# signal_generator_schematic_-_botttom.net
KiCad netlist of a schematic drawn in EAGLE
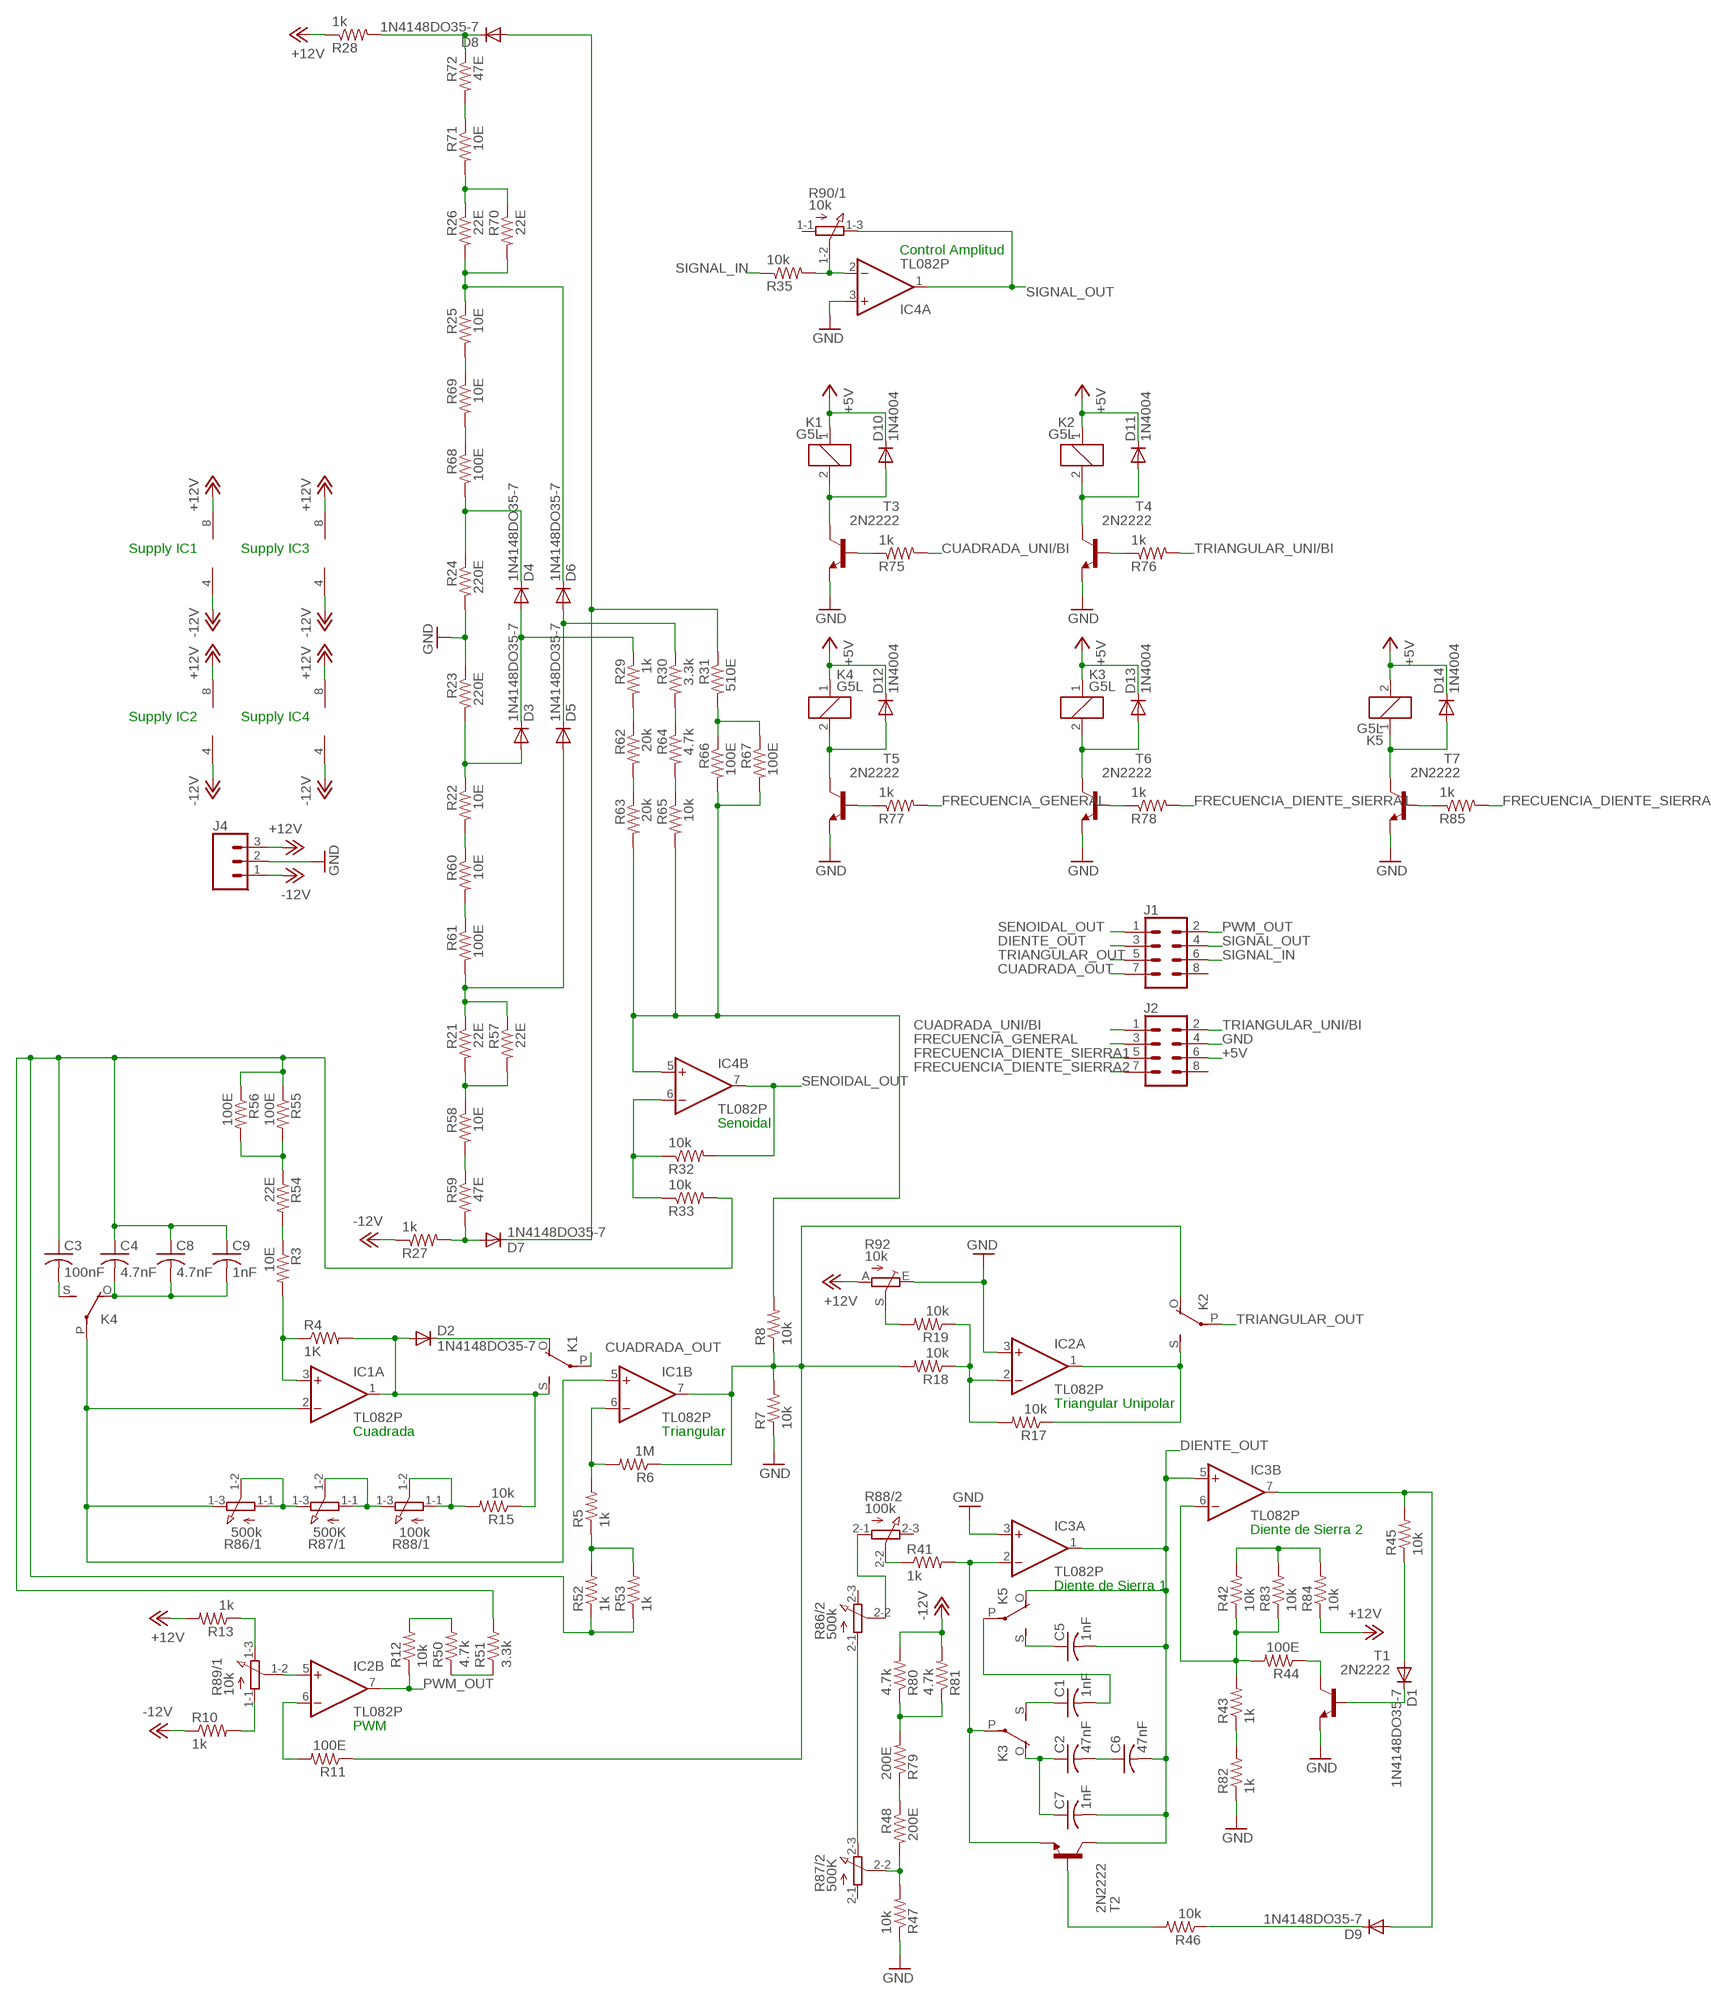
[diagram p0: schematic, sheet 1]

(export (version "E")
  (design (tool "Eeschema 10.0.6"))
  (components
    (comp (ref "C1")
      (value "1nF")
      (footprint "eagle-import:C150-054X183")
      (libsource (lib "eagle-import") (part "C-US150-054X183"))
    )
    (comp (ref "C2")
      (value "47nF")
      (footprint "eagle-import:C150-054X183")
      (libsource (lib "eagle-import") (part "C-US150-054X183"))
    )
    (comp (ref "C3")
      (value "100nF")
      (footprint "eagle-import:C150-084X183")
      (libsource (lib "eagle-import") (part "C-US150-084X183"))
    )
    (comp (ref "C4")
      (value "4.7nF")
      (footprint "eagle-import:C102-043X133")
      (libsource (lib "eagle-import") (part "C-US102-043X133"))
    )
    (comp (ref "C5")
      (value "1nF")
      (footprint "eagle-import:C150-054X183")
      (libsource (lib "eagle-import") (part "C-US150-054X183"))
    )
    (comp (ref "C6")
      (value "47nF")
      (footprint "eagle-import:C150-054X183")
      (libsource (lib "eagle-import") (part "C-US150-054X183"))
    )
    (comp (ref "C7")
      (value "1nF")
      (footprint "eagle-import:C150-054X183")
      (libsource (lib "eagle-import") (part "C-US150-054X183"))
    )
    (comp (ref "C8")
      (value "4.7nF")
      (footprint "eagle-import:C102-043X133")
      (libsource (lib "eagle-import") (part "C-US102-043X133"))
    )
    (comp (ref "C9")
      (value "1nF")
      (footprint "eagle-import:C150-054X183")
      (libsource (lib "eagle-import") (part "C-US150-054X183"))
    )
    (comp (ref "D1")
      (value "1N4148DO35-7")
      (footprint "eagle-import:DO35-7")
      (libsource (lib "eagle-import") (part "1N4148DO35-7"))
    )
    (comp (ref "D2")
      (value "1N4148DO35-7")
      (footprint "eagle-import:DO35-7")
      (libsource (lib "eagle-import") (part "1N4148DO35-7"))
    )
    (comp (ref "D3")
      (value "1N4148DO35-7")
      (footprint "eagle-import:DO35-7")
      (libsource (lib "eagle-import") (part "1N4148DO35-7"))
    )
    (comp (ref "D4")
      (value "1N4148DO35-7")
      (footprint "eagle-import:DO35-7")
      (libsource (lib "eagle-import") (part "1N4148DO35-7"))
    )
    (comp (ref "D5")
      (value "1N4148DO35-7")
      (footprint "eagle-import:DO35-7")
      (libsource (lib "eagle-import") (part "1N4148DO35-7"))
    )
    (comp (ref "D6")
      (value "1N4148DO35-7")
      (footprint "eagle-import:DO35-7")
      (libsource (lib "eagle-import") (part "1N4148DO35-7"))
    )
    (comp (ref "D7")
      (value "1N4148DO35-7")
      (footprint "eagle-import:DO35-7")
      (libsource (lib "eagle-import") (part "1N4148DO35-7"))
    )
    (comp (ref "D8")
      (value "1N4148DO35-7")
      (footprint "eagle-import:DO35-7")
      (libsource (lib "eagle-import") (part "1N4148DO35-7"))
    )
    (comp (ref "D9")
      (value "1N4148DO35-7")
      (footprint "eagle-import:DO35-7")
      (libsource (lib "eagle-import") (part "1N4148DO35-7"))
    )
    (comp (ref "D10")
      (value "1N4004")
      (footprint "eagle-import:DO41-10")
      (libsource (lib "eagle-import") (part "1N4004"))
    )
    (comp (ref "D11")
      (value "1N4004")
      (footprint "eagle-import:DO41-10")
      (libsource (lib "eagle-import") (part "1N4004"))
    )
    (comp (ref "D12")
      (value "1N4004")
      (footprint "eagle-import:DO41-10")
      (libsource (lib "eagle-import") (part "1N4004"))
    )
    (comp (ref "D13")
      (value "1N4004")
      (footprint "eagle-import:DO41-10")
      (libsource (lib "eagle-import") (part "1N4004"))
    )
    (comp (ref "D14")
      (value "1N4004")
      (footprint "eagle-import:DO41-10")
      (libsource (lib "eagle-import") (part "1N4004"))
    )
    (comp (ref "IC1")
      (value "TL082P")
      (footprint "eagle-import:DIL08")
      (libsource (lib "eagle-import") (part "TL082P"))
    )
    (comp (ref "IC2")
      (value "TL082P")
      (footprint "eagle-import:DIL08")
      (libsource (lib "eagle-import") (part "TL082P"))
    )
    (comp (ref "IC3")
      (value "TL082P")
      (footprint "eagle-import:DIL08")
      (libsource (lib "eagle-import") (part "TL082P"))
    )
    (comp (ref "IC4")
      (value "TL082P")
      (footprint "eagle-import:DIL08")
      (libsource (lib "eagle-import") (part "TL082P"))
    )
    (comp (ref "J1")
      (value "CONN_04X2")
      (footprint "eagle-import:2X4")
      (libsource (lib "eagle-import") (part "CONN_04X2"))
    )
    (comp (ref "J2")
      (value "CONN_04X2")
      (footprint "eagle-import:2X4")
      (libsource (lib "eagle-import") (part "CONN_04X2"))
    )
    (comp (ref "J4")
      (value "CONN_03-SCREW-5MM")
      (footprint "eagle-import:SCREWTERMINAL-5MM-3")
      (libsource (lib "eagle-import") (part "CONN_03-SCREW-5MM"))
    )
    (comp (ref "K1")
      (value "G5L")
      (footprint "eagle-import:G5LE")
      (libsource (lib "eagle-import") (part "G5L"))
    )
    (comp (ref "K2")
      (value "G5L")
      (footprint "eagle-import:G5LE")
      (libsource (lib "eagle-import") (part "G5L"))
    )
    (comp (ref "K3")
      (value "G5L")
      (footprint "eagle-import:G5LE")
      (libsource (lib "eagle-import") (part "G5L"))
    )
    (comp (ref "K4")
      (value "G5L")
      (footprint "eagle-import:G5LE")
      (libsource (lib "eagle-import") (part "G5L"))
    )
    (comp (ref "K5")
      (value "G5L")
      (footprint "eagle-import:G5LE")
      (libsource (lib "eagle-import") (part "G5L"))
    )
    (comp (ref "R3")
      (value "10E")
      (footprint "eagle-import:0207_7")
      (libsource (lib "eagle-import") (part "R-US_0207/7"))
    )
    (comp (ref "R4")
      (value "1K")
      (footprint "eagle-import:0207_7")
      (libsource (lib "eagle-import") (part "R-US_0207/7"))
    )
    (comp (ref "R5")
      (value "1k")
      (footprint "eagle-import:0207_7")
      (libsource (lib "eagle-import") (part "R-US_0207/7"))
    )
    (comp (ref "R6")
      (value "1M")
      (footprint "eagle-import:0207_7")
      (libsource (lib "eagle-import") (part "R-US_0207/7"))
    )
    (comp (ref "R7")
      (value "10k")
      (footprint "eagle-import:0207_7")
      (libsource (lib "eagle-import") (part "R-US_0207/7"))
    )
    (comp (ref "R8")
      (value "10k")
      (footprint "eagle-import:0207_7")
      (libsource (lib "eagle-import") (part "R-US_0207/7"))
    )
    (comp (ref "R10")
      (value "1k")
      (footprint "eagle-import:0207_7")
      (libsource (lib "eagle-import") (part "R-US_0207/7"))
    )
    (comp (ref "R11")
      (value "100E")
      (footprint "eagle-import:0207_7")
      (libsource (lib "eagle-import") (part "R-US_0207/7"))
    )
    (comp (ref "R12")
      (value "10k")
      (footprint "eagle-import:0207_7")
      (libsource (lib "eagle-import") (part "R-US_0207/7"))
    )
    (comp (ref "R13")
      (value "1k")
      (footprint "eagle-import:0207_7")
      (libsource (lib "eagle-import") (part "R-US_0207/7"))
    )
    (comp (ref "R15")
      (value "10k")
      (footprint "eagle-import:0207_7")
      (libsource (lib "eagle-import") (part "R-US_0207/7"))
    )
    (comp (ref "R17")
      (value "10k")
      (footprint "eagle-import:0207_7")
      (libsource (lib "eagle-import") (part "R-US_0207/7"))
    )
    (comp (ref "R18")
      (value "10k")
      (footprint "eagle-import:0207_7")
      (libsource (lib "eagle-import") (part "R-US_0207/7"))
    )
    (comp (ref "R19")
      (value "10k")
      (footprint "eagle-import:0207_7")
      (libsource (lib "eagle-import") (part "R-US_0207/7"))
    )
    (comp (ref "R21")
      (value "22E")
      (footprint "eagle-import:0207_7")
      (libsource (lib "eagle-import") (part "R-US_0207/7"))
    )
    (comp (ref "R22")
      (value "10E")
      (footprint "eagle-import:0207_7")
      (libsource (lib "eagle-import") (part "R-US_0207/7"))
    )
    (comp (ref "R23")
      (value "220E")
      (footprint "eagle-import:0207_7")
      (libsource (lib "eagle-import") (part "R-US_0207/7"))
    )
    (comp (ref "R24")
      (value "220E")
      (footprint "eagle-import:0207_7")
      (libsource (lib "eagle-import") (part "R-US_0207/7"))
    )
    (comp (ref "R25")
      (value "10E")
      (footprint "eagle-import:0207_7")
      (libsource (lib "eagle-import") (part "R-US_0207/7"))
    )
    (comp (ref "R26")
      (value "22E")
      (footprint "eagle-import:0207_7")
      (libsource (lib "eagle-import") (part "R-US_0207/7"))
    )
    (comp (ref "R27")
      (value "1k")
      (footprint "eagle-import:0207_7")
      (libsource (lib "eagle-import") (part "R-US_0207/7"))
    )
    (comp (ref "R28")
      (value "1k")
      (footprint "eagle-import:0207_7")
      (libsource (lib "eagle-import") (part "R-US_0207/7"))
    )
    (comp (ref "R29")
      (value "1k")
      (footprint "eagle-import:0207_7")
      (libsource (lib "eagle-import") (part "R-US_0207/7"))
    )
    (comp (ref "R30")
      (value "3.3k")
      (footprint "eagle-import:0207_7")
      (libsource (lib "eagle-import") (part "R-US_0207/7"))
    )
    (comp (ref "R31")
      (value "510E")
      (footprint "eagle-import:0207_7")
      (libsource (lib "eagle-import") (part "R-US_0207/7"))
    )
    (comp (ref "R32")
      (value "10k")
      (footprint "eagle-import:0207_7")
      (libsource (lib "eagle-import") (part "R-US_0207/7"))
    )
    (comp (ref "R33")
      (value "10k")
      (footprint "eagle-import:0207_7")
      (libsource (lib "eagle-import") (part "R-US_0207/7"))
    )
    (comp (ref "R35")
      (value "10k")
      (footprint "eagle-import:0207_7")
      (libsource (lib "eagle-import") (part "R-US_0207/7"))
    )
    (comp (ref "R41")
      (value "1k")
      (footprint "eagle-import:0207_7")
      (libsource (lib "eagle-import") (part "R-US_0207/7"))
    )
    (comp (ref "R42")
      (value "10k")
      (footprint "eagle-import:0207_7")
      (libsource (lib "eagle-import") (part "R-US_0207/7"))
    )
    (comp (ref "R43")
      (value "1k")
      (footprint "eagle-import:0207_7")
      (libsource (lib "eagle-import") (part "R-US_0207/7"))
    )
    (comp (ref "R44")
      (value "100E")
      (footprint "eagle-import:0207_7")
      (libsource (lib "eagle-import") (part "R-US_0207/7"))
    )
    (comp (ref "R45")
      (value "10k")
      (footprint "eagle-import:0207_7")
      (libsource (lib "eagle-import") (part "R-US_0207/7"))
    )
    (comp (ref "R46")
      (value "10k")
      (footprint "eagle-import:0207_7")
      (libsource (lib "eagle-import") (part "R-US_0207/7"))
    )
    (comp (ref "R47")
      (value "10k")
      (footprint "eagle-import:0207_7")
      (libsource (lib "eagle-import") (part "R-US_0207/7"))
    )
    (comp (ref "R48")
      (value "200E")
      (footprint "eagle-import:0207_7")
      (libsource (lib "eagle-import") (part "R-US_0207/7"))
    )
    (comp (ref "R50")
      (value "4.7k")
      (footprint "eagle-import:0207_7")
      (libsource (lib "eagle-import") (part "R-US_0207/7"))
    )
    (comp (ref "R51")
      (value "3.3k")
      (footprint "eagle-import:0207_7")
      (libsource (lib "eagle-import") (part "R-US_0207/7"))
    )
    (comp (ref "R52")
      (value "1k")
      (footprint "eagle-import:0207_7")
      (libsource (lib "eagle-import") (part "R-US_0207/7"))
    )
    (comp (ref "R53")
      (value "1k")
      (footprint "eagle-import:0207_7")
      (libsource (lib "eagle-import") (part "R-US_0207/7"))
    )
    (comp (ref "R54")
      (value "22E")
      (footprint "eagle-import:0207_7")
      (libsource (lib "eagle-import") (part "R-US_0207/7"))
    )
    (comp (ref "R55")
      (value "100E")
      (footprint "eagle-import:0207_7")
      (libsource (lib "eagle-import") (part "R-US_0207/7"))
    )
    (comp (ref "R56")
      (value "100E")
      (footprint "eagle-import:0207_7")
      (libsource (lib "eagle-import") (part "R-US_0207/7"))
    )
    (comp (ref "R57")
      (value "22E")
      (footprint "eagle-import:0207_7")
      (libsource (lib "eagle-import") (part "R-US_0207/7"))
    )
    (comp (ref "R58")
      (value "10E")
      (footprint "eagle-import:0207_7")
      (libsource (lib "eagle-import") (part "R-US_0207/7"))
    )
    (comp (ref "R59")
      (value "47E")
      (footprint "eagle-import:0207_7")
      (libsource (lib "eagle-import") (part "R-US_0207/7"))
    )
    (comp (ref "R60")
      (value "10E")
      (footprint "eagle-import:0207_7")
      (libsource (lib "eagle-import") (part "R-US_0207/7"))
    )
    (comp (ref "R61")
      (value "100E")
      (footprint "eagle-import:0207_7")
      (libsource (lib "eagle-import") (part "R-US_0207/7"))
    )
    (comp (ref "R62")
      (value "20k")
      (footprint "eagle-import:0207_7")
      (libsource (lib "eagle-import") (part "R-US_0207/7"))
    )
    (comp (ref "R63")
      (value "20k")
      (footprint "eagle-import:0207_7")
      (libsource (lib "eagle-import") (part "R-US_0207/7"))
    )
    (comp (ref "R64")
      (value "4.7k")
      (footprint "eagle-import:0207_7")
      (libsource (lib "eagle-import") (part "R-US_0207/7"))
    )
    (comp (ref "R65")
      (value "10k")
      (footprint "eagle-import:0207_7")
      (libsource (lib "eagle-import") (part "R-US_0207/7"))
    )
    (comp (ref "R66")
      (value "100E")
      (footprint "eagle-import:0207_7")
      (libsource (lib "eagle-import") (part "R-US_0207/7"))
    )
    (comp (ref "R67")
      (value "100E")
      (footprint "eagle-import:0207_7")
      (libsource (lib "eagle-import") (part "R-US_0207/7"))
    )
    (comp (ref "R68")
      (value "100E")
      (footprint "eagle-import:0207_7")
      (libsource (lib "eagle-import") (part "R-US_0207/7"))
    )
    (comp (ref "R69")
      (value "10E")
      (footprint "eagle-import:0207_7")
      (libsource (lib "eagle-import") (part "R-US_0207/7"))
    )
    (comp (ref "R70")
      (value "22E")
      (footprint "eagle-import:0207_7")
      (libsource (lib "eagle-import") (part "R-US_0207/7"))
    )
    (comp (ref "R71")
      (value "10E")
      (footprint "eagle-import:0207_7")
      (libsource (lib "eagle-import") (part "R-US_0207/7"))
    )
    (comp (ref "R72")
      (value "47E")
      (footprint "eagle-import:0207_7")
      (libsource (lib "eagle-import") (part "R-US_0207/7"))
    )
    (comp (ref "R75")
      (value "1k")
      (footprint "eagle-import:0207_7")
      (libsource (lib "eagle-import") (part "R-US_0207/7"))
    )
    (comp (ref "R76")
      (value "1k")
      (footprint "eagle-import:0207_7")
      (libsource (lib "eagle-import") (part "R-US_0207/7"))
    )
    (comp (ref "R77")
      (value "1k")
      (footprint "eagle-import:0207_7")
      (libsource (lib "eagle-import") (part "R-US_0207/7"))
    )
    (comp (ref "R78")
      (value "1k")
      (footprint "eagle-import:0207_7")
      (libsource (lib "eagle-import") (part "R-US_0207/7"))
    )
    (comp (ref "R79")
      (value "200E")
      (footprint "eagle-import:0207_7")
      (libsource (lib "eagle-import") (part "R-US_0207/7"))
    )
    (comp (ref "R80")
      (value "4.7k")
      (footprint "eagle-import:0207_7")
      (libsource (lib "eagle-import") (part "R-US_0207/7"))
    )
    (comp (ref "R81")
      (value "4.7k")
      (footprint "eagle-import:0207_7")
      (libsource (lib "eagle-import") (part "R-US_0207/7"))
    )
    (comp (ref "R82")
      (value "1k")
      (footprint "eagle-import:0207_7")
      (libsource (lib "eagle-import") (part "R-US_0207/7"))
    )
    (comp (ref "R83")
      (value "10k")
      (footprint "eagle-import:0207_7")
      (libsource (lib "eagle-import") (part "R-US_0207/7"))
    )
    (comp (ref "R84")
      (value "10k")
      (footprint "eagle-import:0207_7")
      (libsource (lib "eagle-import") (part "R-US_0207/7"))
    )
    (comp (ref "R85")
      (value "1k")
      (footprint "eagle-import:0207_7")
      (libsource (lib "eagle-import") (part "R-US_0207/7"))
    )
    (comp (ref "R86")
      (value "500k")
      (footprint "eagle-import:3RP_1610G")
      (libsource (lib "eagle-import") (part "3RP/1610G"))
    )
    (comp (ref "R87")
      (value "500K")
      (footprint "eagle-import:3RP_1610G")
      (libsource (lib "eagle-import") (part "3RP/1610G"))
    )
    (comp (ref "R88")
      (value "100k")
      (footprint "eagle-import:3RP_1610G")
      (libsource (lib "eagle-import") (part "3RP/1610G"))
    )
    (comp (ref "R89")
      (value "10k")
      (footprint "eagle-import:3RP_1610G")
      (libsource (lib "eagle-import") (part "3RP/1610G"))
    )
    (comp (ref "R90")
      (value "10k")
      (footprint "eagle-import:3RP_1610G")
      (libsource (lib "eagle-import") (part "3RP/1610G"))
    )
    (comp (ref "R92")
      (value "10k")
      (footprint "eagle-import:S63P")
      (libsource (lib "eagle-import") (part "TRIM_EU-S63P"))
    )
    (comp (ref "T1")
      (value "2N2222")
      (footprint "eagle-import:TO92-EBC-OVAL")
      (libsource (lib "eagle-import") (part "2N2222"))
    )
    (comp (ref "T2")
      (value "2N2222")
      (footprint "eagle-import:TO92-EBC-OVAL")
      (libsource (lib "eagle-import") (part "2N2222"))
    )
    (comp (ref "T3")
      (value "2N2222")
      (footprint "eagle-import:TO92-EBC-OVAL")
      (libsource (lib "eagle-import") (part "2N2222"))
    )
    (comp (ref "T4")
      (value "2N2222")
      (footprint "eagle-import:TO92-EBC-OVAL")
      (libsource (lib "eagle-import") (part "2N2222"))
    )
    (comp (ref "T5")
      (value "2N2222")
      (footprint "eagle-import:TO92-EBC-OVAL")
      (libsource (lib "eagle-import") (part "2N2222"))
    )
    (comp (ref "T6")
      (value "2N2222")
      (footprint "eagle-import:TO92-EBC-OVAL")
      (libsource (lib "eagle-import") (part "2N2222"))
    )
    (comp (ref "T7")
      (value "2N2222")
      (footprint "eagle-import:TO92-EBC-OVAL")
      (libsource (lib "eagle-import") (part "2N2222"))
    )
  )
  (nets
    (net (code "1") (name "+5V") (class "Default")
      (node (ref "D10") (pin "C") (pinfunction "C_C") (pintype "passive"))
      (node (ref "D11") (pin "C") (pinfunction "C_C") (pintype "passive"))
      (node (ref "D12") (pin "C") (pinfunction "C_C") (pintype "passive"))
      (node (ref "D13") (pin "C") (pinfunction "C_C") (pintype "passive"))
      (node (ref "D14") (pin "C") (pinfunction "C_C") (pintype "passive"))
      (node (ref "J2") (pin "6") (pinfunction "6_6") (pintype "passive"))
      (node (ref "K1") (pin "1") (pinfunction "1_1") (pintype "passive"))
      (node (ref "K2") (pin "1") (pinfunction "1_1") (pintype "passive"))
      (node (ref "K3") (pin "1") (pinfunction "1_1") (pintype "passive"))
      (node (ref "K4") (pin "1") (pinfunction "1_1") (pintype "passive"))
      (node (ref "K5") (pin "2") (pinfunction "2_2") (pintype "passive"))
    )
    (net (code "2") (name "+12V") (class "Default")
      (node (ref "IC1") (pin "8") (pinfunction "V+_8") (pintype "power_in"))
      (node (ref "IC2") (pin "8") (pinfunction "V+_8") (pintype "power_in"))
      (node (ref "IC3") (pin "8") (pinfunction "V+_8") (pintype "power_in"))
      (node (ref "IC4") (pin "8") (pinfunction "V+_8") (pintype "power_in"))
      (node (ref "J4") (pin "3") (pinfunction "3_3") (pintype "passive"))
      (node (ref "R13") (pin "2") (pinfunction "2_2") (pintype "passive"))
      (node (ref "R28") (pin "1") (pinfunction "1_1") (pintype "passive"))
      (node (ref "R84") (pin "1") (pinfunction "1_1") (pintype "passive"))
      (node (ref "R92") (pin "A") (pinfunction "A_A") (pintype "passive"))
    )
    (net (code "3") (name "-12V") (class "Default")
      (node (ref "IC1") (pin "4") (pinfunction "V-_4") (pintype "power_in"))
      (node (ref "IC2") (pin "4") (pinfunction "V-_4") (pintype "power_in"))
      (node (ref "IC3") (pin "4") (pinfunction "V-_4") (pintype "power_in"))
      (node (ref "IC4") (pin "4") (pinfunction "V-_4") (pintype "power_in"))
      (node (ref "J4") (pin "1") (pinfunction "1_1") (pintype "passive"))
      (node (ref "R10") (pin "1") (pinfunction "1_1") (pintype "passive"))
      (node (ref "R27") (pin "1") (pinfunction "1_1") (pintype "passive"))
      (node (ref "R80") (pin "2") (pinfunction "2_2") (pintype "passive"))
      (node (ref "R81") (pin "2") (pinfunction "2_2") (pintype "passive"))
    )
    (net (code "4") (name "/CUADRADA_OUT") (class "Default")
      (node (ref "J1") (pin "7") (pinfunction "7_7") (pintype "passive"))
      (node (ref "K1") (pin "P") (pinfunction "P_P") (pintype "passive"))
    )
    (net (code "5") (name "/CUADRADA_UNI{slash}BI") (class "Default")
      (node (ref "J2") (pin "1") (pinfunction "1_1") (pintype "passive"))
      (node (ref "R75") (pin "2") (pinfunction "2_2") (pintype "passive"))
    )
    (net (code "6") (name "/DIENTE_OUT") (class "Default")
      (node (ref "C5") (pin "2") (pinfunction "2_2") (pintype "passive"))
      (node (ref "C6") (pin "2") (pinfunction "2_2") (pintype "passive"))
      (node (ref "C7") (pin "2") (pinfunction "2_2") (pintype "passive"))
      (node (ref "IC3") (pin "1") (pinfunction "OUT_1") (pintype "output"))
      (node (ref "IC3") (pin "5") (pinfunction "+IN_5") (pintype "input"))
      (node (ref "J1") (pin "3") (pinfunction "3_3") (pintype "passive"))
      (node (ref "K5") (pin "O") (pinfunction "O_O") (pintype "passive"))
      (node (ref "T2") (pin "C") (pinfunction "C_C") (pintype "passive"))
    )
    (net (code "7") (name "/FRECUENCIA_DIENTE_SIERRA1") (class "Default")
      (node (ref "J2") (pin "5") (pinfunction "5_5") (pintype "passive"))
      (node (ref "R78") (pin "2") (pinfunction "2_2") (pintype "passive"))
    )
    (net (code "8") (name "/FRECUENCIA_DIENTE_SIERRA2") (class "Default")
      (node (ref "J2") (pin "7") (pinfunction "7_7") (pintype "passive"))
      (node (ref "R85") (pin "2") (pinfunction "2_2") (pintype "passive"))
    )
    (net (code "9") (name "/FRECUENCIA_GENERAL") (class "Default")
      (node (ref "J2") (pin "3") (pinfunction "3_3") (pintype "passive"))
      (node (ref "R77") (pin "2") (pinfunction "2_2") (pintype "passive"))
    )
    (net (code "10") (name "/PWM_OUT") (class "Default")
      (node (ref "IC2") (pin "7") (pinfunction "OUT_7") (pintype "output"))
      (node (ref "J1") (pin "2") (pinfunction "2_2") (pintype "passive"))
      (node (ref "R12") (pin "1") (pinfunction "1_1") (pintype "passive"))
    )
    (net (code "11") (name "/SENOIDAL_OUT") (class "Default")
      (node (ref "IC4") (pin "7") (pinfunction "OUT_7") (pintype "output"))
      (node (ref "J1") (pin "1") (pinfunction "1_1") (pintype "passive"))
      (node (ref "R32") (pin "2") (pinfunction "2_2") (pintype "passive"))
    )
    (net (code "12") (name "/SIGNAL_IN") (class "Default")
      (node (ref "J1") (pin "6") (pinfunction "6_6") (pintype "passive"))
      (node (ref "R35") (pin "1") (pinfunction "1_1") (pintype "passive"))
    )
    (net (code "13") (name "/SIGNAL_OUT") (class "Default")
      (node (ref "IC4") (pin "1") (pinfunction "OUT_1") (pintype "output"))
      (node (ref "J1") (pin "4") (pinfunction "4_4") (pintype "passive"))
      (node (ref "R90") (pin "1-3") (pinfunction "E_1-3") (pintype "passive"))
    )
    (net (code "14") (name "/TRIANGULAR_OUT") (class "Default")
      (node (ref "J1") (pin "5") (pinfunction "5_5") (pintype "passive"))
      (node (ref "K2") (pin "P") (pinfunction "P_P") (pintype "passive"))
    )
    (net (code "15") (name "/TRIANGULAR_UNI{slash}BI") (class "Default")
      (node (ref "J2") (pin "2") (pinfunction "2_2") (pintype "passive"))
      (node (ref "R76") (pin "2") (pinfunction "2_2") (pintype "passive"))
    )
    (net (code "16") (name "GND") (class "Default")
      (node (ref "IC2") (pin "3") (pinfunction "+IN_3") (pintype "input"))
      (node (ref "IC3") (pin "3") (pinfunction "+IN_3") (pintype "input"))
      (node (ref "IC4") (pin "3") (pinfunction "+IN_3") (pintype "input"))
      (node (ref "J2") (pin "4") (pinfunction "4_4") (pintype "passive"))
      (node (ref "J4") (pin "2") (pinfunction "2_2") (pintype "passive"))
      (node (ref "R23") (pin "1") (pinfunction "1_1") (pintype "passive"))
      (node (ref "R24") (pin "2") (pinfunction "2_2") (pintype "passive"))
      (node (ref "R47") (pin "1") (pinfunction "1_1") (pintype "passive"))
      (node (ref "R7") (pin "1") (pinfunction "1_1") (pintype "passive"))
      (node (ref "R82") (pin "1") (pinfunction "1_1") (pintype "passive"))
      (node (ref "R92") (pin "E") (pinfunction "E_E") (pintype "passive"))
      (node (ref "T1") (pin "E") (pinfunction "E_E") (pintype "passive"))
      (node (ref "T3") (pin "E") (pinfunction "E_E") (pintype "passive"))
      (node (ref "T4") (pin "E") (pinfunction "E_E") (pintype "passive"))
      (node (ref "T5") (pin "E") (pinfunction "E_E") (pintype "passive"))
      (node (ref "T6") (pin "E") (pinfunction "E_E") (pintype "passive"))
      (node (ref "T7") (pin "E") (pinfunction "E_E") (pintype "passive"))
    )
    (net (code "17") (name "Net-(C1-Pad1)") (class "Default")
      (node (ref "C1") (pin "1") (pinfunction "1_1") (pintype "passive"))
      (node (ref "K3") (pin "S") (pinfunction "S_S") (pintype "passive"))
    )
    (net (code "18") (name "Net-(C1-Pad2)") (class "Default")
      (node (ref "C1") (pin "2") (pinfunction "2_2") (pintype "passive"))
      (node (ref "K5") (pin "P") (pinfunction "P_P") (pintype "passive"))
    )
    (net (code "19") (name "Net-(C2-Pad1)") (class "Default")
      (node (ref "C2") (pin "1") (pinfunction "1_1") (pintype "passive"))
      (node (ref "C7") (pin "1") (pinfunction "1_1") (pintype "passive"))
      (node (ref "K3") (pin "O") (pinfunction "O_O") (pintype "passive"))
    )
    (net (code "20") (name "Net-(C2-Pad2)") (class "Default")
      (node (ref "C2") (pin "2") (pinfunction "2_2") (pintype "passive"))
      (node (ref "C6") (pin "1") (pinfunction "1_1") (pintype "passive"))
    )
    (net (code "21") (name "Net-(C3-Pad1)") (class "Default")
      (node (ref "C3") (pin "1") (pinfunction "1_1") (pintype "passive"))
      (node (ref "C4") (pin "1") (pinfunction "1_1") (pintype "passive"))
      (node (ref "C8") (pin "1") (pinfunction "1_1") (pintype "passive"))
      (node (ref "C9") (pin "1") (pinfunction "1_1") (pintype "passive"))
      (node (ref "R33") (pin "2") (pinfunction "2_2") (pintype "passive"))
      (node (ref "R51") (pin "2") (pinfunction "2_2") (pintype "passive"))
      (node (ref "R52") (pin "1") (pinfunction "1_1") (pintype "passive"))
      (node (ref "R53") (pin "1") (pinfunction "1_1") (pintype "passive"))
      (node (ref "R55") (pin "1") (pinfunction "1_1") (pintype "passive"))
      (node (ref "R56") (pin "1") (pinfunction "1_1") (pintype "passive"))
    )
    (net (code "22") (name "Net-(C3-Pad2)") (class "Default")
      (node (ref "C3") (pin "2") (pinfunction "2_2") (pintype "passive"))
      (node (ref "K4") (pin "S") (pinfunction "S_S") (pintype "passive"))
    )
    (net (code "23") (name "Net-(C4-Pad2)") (class "Default")
      (node (ref "C4") (pin "2") (pinfunction "2_2") (pintype "passive"))
      (node (ref "C8") (pin "2") (pinfunction "2_2") (pintype "passive"))
      (node (ref "C9") (pin "2") (pinfunction "2_2") (pintype "passive"))
      (node (ref "K4") (pin "O") (pinfunction "O_O") (pintype "passive"))
    )
    (net (code "24") (name "Net-(C5-Pad1)") (class "Default")
      (node (ref "C5") (pin "1") (pinfunction "1_1") (pintype "passive"))
      (node (ref "K5") (pin "S") (pinfunction "S_S") (pintype "passive"))
    )
    (net (code "25") (name "Net-(D1-PadA)") (class "Default")
      (node (ref "D1") (pin "A") (pinfunction "A_A") (pintype "passive"))
      (node (ref "R45") (pin "1") (pinfunction "1_1") (pintype "passive"))
    )
    (net (code "26") (name "Net-(D1-PadC)") (class "Default")
      (node (ref "D1") (pin "C") (pinfunction "C_C") (pintype "passive"))
      (node (ref "T1") (pin "B") (pinfunction "B_B") (pintype "passive"))
    )
    (net (code "27") (name "Net-(D2-PadC)") (class "Default")
      (node (ref "D2") (pin "C") (pinfunction "C_C") (pintype "passive"))
      (node (ref "K1") (pin "O") (pinfunction "O_O") (pintype "passive"))
    )
    (net (code "28") (name "Net-(D3-PadA)") (class "Default")
      (node (ref "D3") (pin "A") (pinfunction "A_A") (pintype "passive"))
      (node (ref "R22") (pin "1") (pinfunction "1_1") (pintype "passive"))
      (node (ref "R23") (pin "2") (pinfunction "2_2") (pintype "passive"))
    )
    (net (code "29") (name "Net-(D3-PadC)") (class "Default")
      (node (ref "D3") (pin "C") (pinfunction "C_C") (pintype "passive"))
      (node (ref "D4") (pin "A") (pinfunction "A_A") (pintype "passive"))
      (node (ref "R29") (pin "1") (pinfunction "1_1") (pintype "passive"))
    )
    (net (code "30") (name "Net-(D4-PadC)") (class "Default")
      (node (ref "D4") (pin "C") (pinfunction "C_C") (pintype "passive"))
      (node (ref "R24") (pin "1") (pinfunction "1_1") (pintype "passive"))
      (node (ref "R68") (pin "2") (pinfunction "2_2") (pintype "passive"))
    )
    (net (code "31") (name "Net-(D5-PadA)") (class "Default")
      (node (ref "D5") (pin "A") (pinfunction "A_A") (pintype "passive"))
      (node (ref "R21") (pin "1") (pinfunction "1_1") (pintype "passive"))
      (node (ref "R57") (pin "1") (pinfunction "1_1") (pintype "passive"))
      (node (ref "R61") (pin "2") (pinfunction "2_2") (pintype "passive"))
    )
    (net (code "32") (name "Net-(D5-PadC)") (class "Default")
      (node (ref "D5") (pin "C") (pinfunction "C_C") (pintype "passive"))
      (node (ref "D6") (pin "A") (pinfunction "A_A") (pintype "passive"))
      (node (ref "R30") (pin "1") (pinfunction "1_1") (pintype "passive"))
    )
    (net (code "33") (name "Net-(D6-PadC)") (class "Default")
      (node (ref "D6") (pin "C") (pinfunction "C_C") (pintype "passive"))
      (node (ref "R25") (pin "1") (pinfunction "1_1") (pintype "passive"))
      (node (ref "R26") (pin "2") (pinfunction "2_2") (pintype "passive"))
      (node (ref "R70") (pin "2") (pinfunction "2_2") (pintype "passive"))
    )
    (net (code "34") (name "Net-(D7-PadA)") (class "Default")
      (node (ref "D7") (pin "A") (pinfunction "A_A") (pintype "passive"))
      (node (ref "R27") (pin "2") (pinfunction "2_2") (pintype "passive"))
      (node (ref "R59") (pin "2") (pinfunction "2_2") (pintype "passive"))
    )
    (net (code "35") (name "Net-(D7-PadC)") (class "Default")
      (node (ref "D7") (pin "C") (pinfunction "C_C") (pintype "passive"))
      (node (ref "D8") (pin "A") (pinfunction "A_A") (pintype "passive"))
      (node (ref "R31") (pin "1") (pinfunction "1_1") (pintype "passive"))
    )
    (net (code "36") (name "Net-(D8-PadC)") (class "Default")
      (node (ref "D8") (pin "C") (pinfunction "C_C") (pintype "passive"))
      (node (ref "R28") (pin "2") (pinfunction "2_2") (pintype "passive"))
      (node (ref "R72") (pin "1") (pinfunction "1_1") (pintype "passive"))
    )
    (net (code "37") (name "Net-(D9-PadC)") (class "Default")
      (node (ref "D9") (pin "C") (pinfunction "C_C") (pintype "passive"))
      (node (ref "R46") (pin "1") (pinfunction "1_1") (pintype "passive"))
    )
    (net (code "38") (name "Net-(D10-PadA)") (class "Default")
      (node (ref "D10") (pin "A") (pinfunction "A_A") (pintype "passive"))
      (node (ref "K1") (pin "2") (pinfunction "2_2") (pintype "passive"))
      (node (ref "T3") (pin "C") (pinfunction "C_C") (pintype "passive"))
    )
    (net (code "39") (name "Net-(D11-PadA)") (class "Default")
      (node (ref "D11") (pin "A") (pinfunction "A_A") (pintype "passive"))
      (node (ref "K2") (pin "2") (pinfunction "2_2") (pintype "passive"))
      (node (ref "T4") (pin "C") (pinfunction "C_C") (pintype "passive"))
    )
    (net (code "40") (name "Net-(D12-PadA)") (class "Default")
      (node (ref "D12") (pin "A") (pinfunction "A_A") (pintype "passive"))
      (node (ref "K4") (pin "2") (pinfunction "2_2") (pintype "passive"))
      (node (ref "T5") (pin "C") (pinfunction "C_C") (pintype "passive"))
    )
    (net (code "41") (name "Net-(D13-PadA)") (class "Default")
      (node (ref "D13") (pin "A") (pinfunction "A_A") (pintype "passive"))
      (node (ref "K3") (pin "2") (pinfunction "2_2") (pintype "passive"))
      (node (ref "T6") (pin "C") (pinfunction "C_C") (pintype "passive"))
    )
    (net (code "42") (name "Net-(D14-PadA)") (class "Default")
      (node (ref "D14") (pin "A") (pinfunction "A_A") (pintype "passive"))
      (node (ref "K5") (pin "1") (pinfunction "1_1") (pintype "passive"))
      (node (ref "T7") (pin "C") (pinfunction "C_C") (pintype "passive"))
    )
    (net (code "43") (name "Net-(IC1A-+IN)") (class "Default")
      (node (ref "IC1") (pin "3") (pinfunction "+IN_3") (pintype "input"))
      (node (ref "R3") (pin "2") (pinfunction "2_2") (pintype "passive"))
      (node (ref "R4") (pin "1") (pinfunction "1_1") (pintype "passive"))
    )
    (net (code "44") (name "Net-(IC1A--IN)") (class "Default")
      (node (ref "IC1") (pin "2") (pinfunction "-IN_2") (pintype "input"))
      (node (ref "IC1") (pin "5") (pinfunction "+IN_5") (pintype "input"))
      (node (ref "K4") (pin "P") (pinfunction "P_P") (pintype "passive"))
      (node (ref "R86") (pin "1-3") (pinfunction "E_1-3") (pintype "passive"))
    )
    (net (code "45") (name "Net-(IC1A-OUT)") (class "Default")
      (node (ref "D2") (pin "A") (pinfunction "A_A") (pintype "passive"))
      (node (ref "IC1") (pin "1") (pinfunction "OUT_1") (pintype "output"))
      (node (ref "K1") (pin "S") (pinfunction "S_S") (pintype "passive"))
      (node (ref "R15") (pin "1") (pinfunction "1_1") (pintype "passive"))
      (node (ref "R4") (pin "2") (pinfunction "2_2") (pintype "passive"))
    )
    (net (code "46") (name "Net-(IC1B--IN)") (class "Default")
      (node (ref "IC1") (pin "6") (pinfunction "-IN_6") (pintype "input"))
      (node (ref "R5") (pin "2") (pinfunction "2_2") (pintype "passive"))
      (node (ref "R6") (pin "2") (pinfunction "2_2") (pintype "passive"))
    )
    (net (code "47") (name "Net-(IC1B-OUT)") (class "Default")
      (node (ref "IC1") (pin "7") (pinfunction "OUT_7") (pintype "output"))
      (node (ref "K2") (pin "O") (pinfunction "O_O") (pintype "passive"))
      (node (ref "R11") (pin "1") (pinfunction "1_1") (pintype "passive"))
      (node (ref "R18") (pin "2") (pinfunction "2_2") (pintype "passive"))
      (node (ref "R6") (pin "1") (pinfunction "1_1") (pintype "passive"))
      (node (ref "R7") (pin "2") (pinfunction "2_2") (pintype "passive"))
      (node (ref "R8") (pin "1") (pinfunction "1_1") (pintype "passive"))
    )
    (net (code "48") (name "Net-(IC2A--IN)") (class "Default")
      (node (ref "IC2") (pin "2") (pinfunction "-IN_2") (pintype "input"))
      (node (ref "R17") (pin "2") (pinfunction "2_2") (pintype "passive"))
      (node (ref "R18") (pin "1") (pinfunction "1_1") (pintype "passive"))
      (node (ref "R19") (pin "1") (pinfunction "1_1") (pintype "passive"))
    )
    (net (code "49") (name "Net-(IC2A-OUT)") (class "Default")
      (node (ref "IC2") (pin "1") (pinfunction "OUT_1") (pintype "output"))
      (node (ref "K2") (pin "S") (pinfunction "S_S") (pintype "passive"))
      (node (ref "R17") (pin "1") (pinfunction "1_1") (pintype "passive"))
    )
    (net (code "50") (name "Net-(IC2B-+IN)") (class "Default")
      (node (ref "IC2") (pin "5") (pinfunction "+IN_5") (pintype "input"))
      (node (ref "R89") (pin "1-2") (pinfunction "S_1-2") (pintype "passive"))
    )
    (net (code "51") (name "Net-(IC2B--IN)") (class "Default")
      (node (ref "IC2") (pin "6") (pinfunction "-IN_6") (pintype "input"))
      (node (ref "R11") (pin "2") (pinfunction "2_2") (pintype "passive"))
    )
    (net (code "52") (name "Net-(IC3A--IN)") (class "Default")
      (node (ref "IC3") (pin "2") (pinfunction "-IN_2") (pintype "input"))
      (node (ref "K3") (pin "P") (pinfunction "P_P") (pintype "passive"))
      (node (ref "R41") (pin "2") (pinfunction "2_2") (pintype "passive"))
      (node (ref "T2") (pin "E") (pinfunction "E_E") (pintype "passive"))
    )
    (net (code "53") (name "Net-(IC3B--IN)") (class "Default")
      (node (ref "IC3") (pin "6") (pinfunction "-IN_6") (pintype "input"))
      (node (ref "R42") (pin "1") (pinfunction "1_1") (pintype "passive"))
      (node (ref "R43") (pin "2") (pinfunction "2_2") (pintype "passive"))
      (node (ref "R44") (pin "2") (pinfunction "2_2") (pintype "passive"))
      (node (ref "R83") (pin "1") (pinfunction "1_1") (pintype "passive"))
    )
    (net (code "54") (name "Net-(IC3B-OUT)") (class "Default")
      (node (ref "D9") (pin "A") (pinfunction "A_A") (pintype "passive"))
      (node (ref "IC3") (pin "7") (pinfunction "OUT_7") (pintype "output"))
      (node (ref "R45") (pin "2") (pinfunction "2_2") (pintype "passive"))
    )
    (net (code "55") (name "Net-(IC4A--IN)") (class "Default")
      (node (ref "IC4") (pin "2") (pinfunction "-IN_2") (pintype "input"))
      (node (ref "R35") (pin "2") (pinfunction "2_2") (pintype "passive"))
      (node (ref "R90") (pin "1-2") (pinfunction "S_1-2") (pintype "passive"))
    )
    (net (code "56") (name "Net-(IC4B-+IN)") (class "Default")
      (node (ref "IC4") (pin "5") (pinfunction "+IN_5") (pintype "input"))
      (node (ref "R63") (pin "2") (pinfunction "2_2") (pintype "passive"))
      (node (ref "R65") (pin "2") (pinfunction "2_2") (pintype "passive"))
      (node (ref "R66") (pin "2") (pinfunction "2_2") (pintype "passive"))
      (node (ref "R67") (pin "2") (pinfunction "2_2") (pintype "passive"))
      (node (ref "R8") (pin "2") (pinfunction "2_2") (pintype "passive"))
    )
    (net (code "57") (name "Net-(IC4B--IN)") (class "Default")
      (node (ref "IC4") (pin "6") (pinfunction "-IN_6") (pintype "input"))
      (node (ref "R32") (pin "1") (pinfunction "1_1") (pintype "passive"))
      (node (ref "R33") (pin "1") (pinfunction "1_1") (pintype "passive"))
    )
    (net (code "58") (name "Net-(R3-Pad1)") (class "Default")
      (node (ref "R3") (pin "1") (pinfunction "1_1") (pintype "passive"))
      (node (ref "R54") (pin "2") (pinfunction "2_2") (pintype "passive"))
    )
    (net (code "59") (name "Net-(R5-Pad1)") (class "Default")
      (node (ref "R5") (pin "1") (pinfunction "1_1") (pintype "passive"))
      (node (ref "R52") (pin "2") (pinfunction "2_2") (pintype "passive"))
      (node (ref "R53") (pin "2") (pinfunction "2_2") (pintype "passive"))
    )
    (net (code "60") (name "Net-(R12-Pad2)") (class "Default")
      (node (ref "R12") (pin "2") (pinfunction "2_2") (pintype "passive"))
      (node (ref "R50") (pin "2") (pinfunction "2_2") (pintype "passive"))
    )
    (net (code "61") (name "Net-(R19-Pad2)") (class "Default")
      (node (ref "R19") (pin "2") (pinfunction "2_2") (pintype "passive"))
      (node (ref "R92") (pin "S") (pinfunction "S_S") (pintype "passive"))
    )
    (net (code "62") (name "Net-(R21-Pad2)") (class "Default")
      (node (ref "R21") (pin "2") (pinfunction "2_2") (pintype "passive"))
      (node (ref "R57") (pin "2") (pinfunction "2_2") (pintype "passive"))
      (node (ref "R58") (pin "1") (pinfunction "1_1") (pintype "passive"))
    )
    (net (code "63") (name "Net-(R22-Pad2)") (class "Default")
      (node (ref "R22") (pin "2") (pinfunction "2_2") (pintype "passive"))
      (node (ref "R60") (pin "1") (pinfunction "1_1") (pintype "passive"))
    )
    (net (code "64") (name "Net-(R25-Pad2)") (class "Default")
      (node (ref "R25") (pin "2") (pinfunction "2_2") (pintype "passive"))
      (node (ref "R69") (pin "1") (pinfunction "1_1") (pintype "passive"))
    )
    (net (code "65") (name "Net-(R26-Pad1)") (class "Default")
      (node (ref "R26") (pin "1") (pinfunction "1_1") (pintype "passive"))
      (node (ref "R70") (pin "1") (pinfunction "1_1") (pintype "passive"))
      (node (ref "R71") (pin "2") (pinfunction "2_2") (pintype "passive"))
    )
    (net (code "66") (name "Net-(R29-Pad2)") (class "Default")
      (node (ref "R29") (pin "2") (pinfunction "2_2") (pintype "passive"))
      (node (ref "R62") (pin "1") (pinfunction "1_1") (pintype "passive"))
    )
    (net (code "67") (name "Net-(R30-Pad2)") (class "Default")
      (node (ref "R30") (pin "2") (pinfunction "2_2") (pintype "passive"))
      (node (ref "R64") (pin "1") (pinfunction "1_1") (pintype "passive"))
    )
    (net (code "68") (name "Net-(R31-Pad2)") (class "Default")
      (node (ref "R31") (pin "2") (pinfunction "2_2") (pintype "passive"))
      (node (ref "R66") (pin "1") (pinfunction "1_1") (pintype "passive"))
      (node (ref "R67") (pin "1") (pinfunction "1_1") (pintype "passive"))
    )
    (net (code "69") (name "Net-(R42-Pad2)") (class "Default")
      (node (ref "R42") (pin "2") (pinfunction "2_2") (pintype "passive"))
      (node (ref "R83") (pin "2") (pinfunction "2_2") (pintype "passive"))
      (node (ref "R84") (pin "2") (pinfunction "2_2") (pintype "passive"))
    )
    (net (code "70") (name "Net-(R43-Pad1)") (class "Default")
      (node (ref "R43") (pin "1") (pinfunction "1_1") (pintype "passive"))
      (node (ref "R82") (pin "2") (pinfunction "2_2") (pintype "passive"))
    )
    (net (code "71") (name "Net-(R44-Pad1)") (class "Default")
      (node (ref "R44") (pin "1") (pinfunction "1_1") (pintype "passive"))
      (node (ref "T1") (pin "C") (pinfunction "C_C") (pintype "passive"))
    )
    (net (code "72") (name "Net-(R46-Pad2)") (class "Default")
      (node (ref "R46") (pin "2") (pinfunction "2_2") (pintype "passive"))
      (node (ref "T2") (pin "B") (pinfunction "B_B") (pintype "passive"))
    )
    (net (code "73") (name "Net-(R48-Pad1)") (class "Default")
      (node (ref "R48") (pin "1") (pinfunction "1_1") (pintype "passive"))
      (node (ref "R79") (pin "1") (pinfunction "1_1") (pintype "passive"))
    )
    (net (code "74") (name "Net-(R50-Pad1)") (class "Default")
      (node (ref "R50") (pin "1") (pinfunction "1_1") (pintype "passive"))
      (node (ref "R51") (pin "1") (pinfunction "1_1") (pintype "passive"))
    )
    (net (code "75") (name "Net-(R54-Pad1)") (class "Default")
      (node (ref "R54") (pin "1") (pinfunction "1_1") (pintype "passive"))
      (node (ref "R55") (pin "2") (pinfunction "2_2") (pintype "passive"))
      (node (ref "R56") (pin "2") (pinfunction "2_2") (pintype "passive"))
    )
    (net (code "76") (name "Net-(R58-Pad2)") (class "Default")
      (node (ref "R58") (pin "2") (pinfunction "2_2") (pintype "passive"))
      (node (ref "R59") (pin "1") (pinfunction "1_1") (pintype "passive"))
    )
    (net (code "77") (name "Net-(R60-Pad2)") (class "Default")
      (node (ref "R60") (pin "2") (pinfunction "2_2") (pintype "passive"))
      (node (ref "R61") (pin "1") (pinfunction "1_1") (pintype "passive"))
    )
    (net (code "78") (name "Net-(R62-Pad2)") (class "Default")
      (node (ref "R62") (pin "2") (pinfunction "2_2") (pintype "passive"))
      (node (ref "R63") (pin "1") (pinfunction "1_1") (pintype "passive"))
    )
    (net (code "79") (name "Net-(R64-Pad2)") (class "Default")
      (node (ref "R64") (pin "2") (pinfunction "2_2") (pintype "passive"))
      (node (ref "R65") (pin "1") (pinfunction "1_1") (pintype "passive"))
    )
    (net (code "80") (name "Net-(R68-Pad1)") (class "Default")
      (node (ref "R68") (pin "1") (pinfunction "1_1") (pintype "passive"))
      (node (ref "R69") (pin "2") (pinfunction "2_2") (pintype "passive"))
    )
    (net (code "81") (name "Net-(R71-Pad1)") (class "Default")
      (node (ref "R71") (pin "1") (pinfunction "1_1") (pintype "passive"))
      (node (ref "R72") (pin "2") (pinfunction "2_2") (pintype "passive"))
    )
    (net (code "82") (name "Net-(R75-Pad1)") (class "Default")
      (node (ref "R75") (pin "1") (pinfunction "1_1") (pintype "passive"))
      (node (ref "T3") (pin "B") (pinfunction "B_B") (pintype "passive"))
    )
    (net (code "83") (name "Net-(R76-Pad1)") (class "Default")
      (node (ref "R76") (pin "1") (pinfunction "1_1") (pintype "passive"))
      (node (ref "T4") (pin "B") (pinfunction "B_B") (pintype "passive"))
    )
    (net (code "84") (name "Net-(R77-Pad1)") (class "Default")
      (node (ref "R77") (pin "1") (pinfunction "1_1") (pintype "passive"))
      (node (ref "T5") (pin "B") (pinfunction "B_B") (pintype "passive"))
    )
    (net (code "85") (name "Net-(R78-Pad1)") (class "Default")
      (node (ref "R78") (pin "1") (pinfunction "1_1") (pintype "passive"))
      (node (ref "T6") (pin "B") (pinfunction "B_B") (pintype "passive"))
    )
    (net (code "86") (name "Net-(R79-Pad2)") (class "Default")
      (node (ref "R79") (pin "2") (pinfunction "2_2") (pintype "passive"))
      (node (ref "R80") (pin "1") (pinfunction "1_1") (pintype "passive"))
      (node (ref "R81") (pin "1") (pinfunction "1_1") (pintype "passive"))
    )
    (net (code "87") (name "Net-(R85-Pad1)") (class "Default")
      (node (ref "R85") (pin "1") (pinfunction "1_1") (pintype "passive"))
      (node (ref "T7") (pin "B") (pinfunction "B_B") (pintype "passive"))
    )
    (net (code "88") (name "Net-(R86A-A)") (class "Default")
      (node (ref "R86") (pin "1-1") (pinfunction "A_1-1") (pintype "passive"))
      (node (ref "R86") (pin "1-2") (pinfunction "S_1-2") (pintype "passive"))
      (node (ref "R87") (pin "1-3") (pinfunction "E_1-3") (pintype "passive"))
    )
    (net (code "89") (name "Net-(R86B-A)") (class "Default")
      (node (ref "R86") (pin "2-1") (pinfunction "A_2-1") (pintype "passive"))
      (node (ref "R87") (pin "2-3") (pinfunction "E_2-3") (pintype "passive"))
    )
    (net (code "90") (name "Net-(R86B-S)") (class "Default")
      (node (ref "R86") (pin "2-2") (pinfunction "S_2-2") (pintype "passive"))
      (node (ref "R88") (pin "2-1") (pinfunction "A_2-1") (pintype "passive"))
    )
    (net (code "91") (name "Net-(R87A-A)") (class "Default")
      (node (ref "R87") (pin "1-1") (pinfunction "A_1-1") (pintype "passive"))
      (node (ref "R87") (pin "1-2") (pinfunction "S_1-2") (pintype "passive"))
      (node (ref "R88") (pin "1-3") (pinfunction "E_1-3") (pintype "passive"))
    )
    (net (code "92") (name "Net-(R87B-S)") (class "Default")
      (node (ref "R47") (pin "2") (pinfunction "2_2") (pintype "passive"))
      (node (ref "R48") (pin "2") (pinfunction "2_2") (pintype "passive"))
      (node (ref "R87") (pin "2-2") (pinfunction "S_2-2") (pintype "passive"))
    )
    (net (code "93") (name "Net-(R88A-A)") (class "Default")
      (node (ref "R15") (pin "2") (pinfunction "2_2") (pintype "passive"))
      (node (ref "R88") (pin "1-1") (pinfunction "A_1-1") (pintype "passive"))
      (node (ref "R88") (pin "1-2") (pinfunction "S_1-2") (pintype "passive"))
    )
    (net (code "94") (name "Net-(R88B-S)") (class "Default")
      (node (ref "R41") (pin "1") (pinfunction "1_1") (pintype "passive"))
      (node (ref "R88") (pin "2-2") (pinfunction "S_2-2") (pintype "passive"))
    )
    (net (code "95") (name "Net-(R89A-A)") (class "Default")
      (node (ref "R10") (pin "2") (pinfunction "2_2") (pintype "passive"))
      (node (ref "R89") (pin "1-1") (pinfunction "A_1-1") (pintype "passive"))
    )
    (net (code "96") (name "Net-(R89A-E)") (class "Default")
      (node (ref "R13") (pin "1") (pinfunction "1_1") (pintype "passive"))
      (node (ref "R89") (pin "1-3") (pinfunction "E_1-3") (pintype "passive"))
    )
    (net (code "97") (name "unconnected-(J1-Pad8)") (class "Default")
      (node (ref "J1") (pin "8") (pinfunction "8_8") (pintype "passive"))
    )
    (net (code "98") (name "unconnected-(J2-Pad8)") (class "Default")
      (node (ref "J2") (pin "8") (pinfunction "8_8") (pintype "passive"))
    )
    (net (code "99") (name "unconnected-(R86B-E-Pad2-3)") (class "Default")
      (node (ref "R86") (pin "2-3") (pinfunction "E_2-3") (pintype "passive"))
    )
    (net (code "100") (name "unconnected-(R87B-A-Pad2-1)") (class "Default")
      (node (ref "R87") (pin "2-1") (pinfunction "A_2-1") (pintype "passive"))
    )
    (net (code "101") (name "unconnected-(R88B-E-Pad2-3)") (class "Default")
      (node (ref "R88") (pin "2-3") (pinfunction "E_2-3") (pintype "passive"))
    )
    (net (code "102") (name "unconnected-(R90A-A-Pad1-1)") (class "Default")
      (node (ref "R90") (pin "1-1") (pinfunction "A_1-1") (pintype "passive"))
    )
  )
)
